# RaspberryPi3_Cape_V1_0.net
KiCad netlist of a schematic drawn in Altium Designer
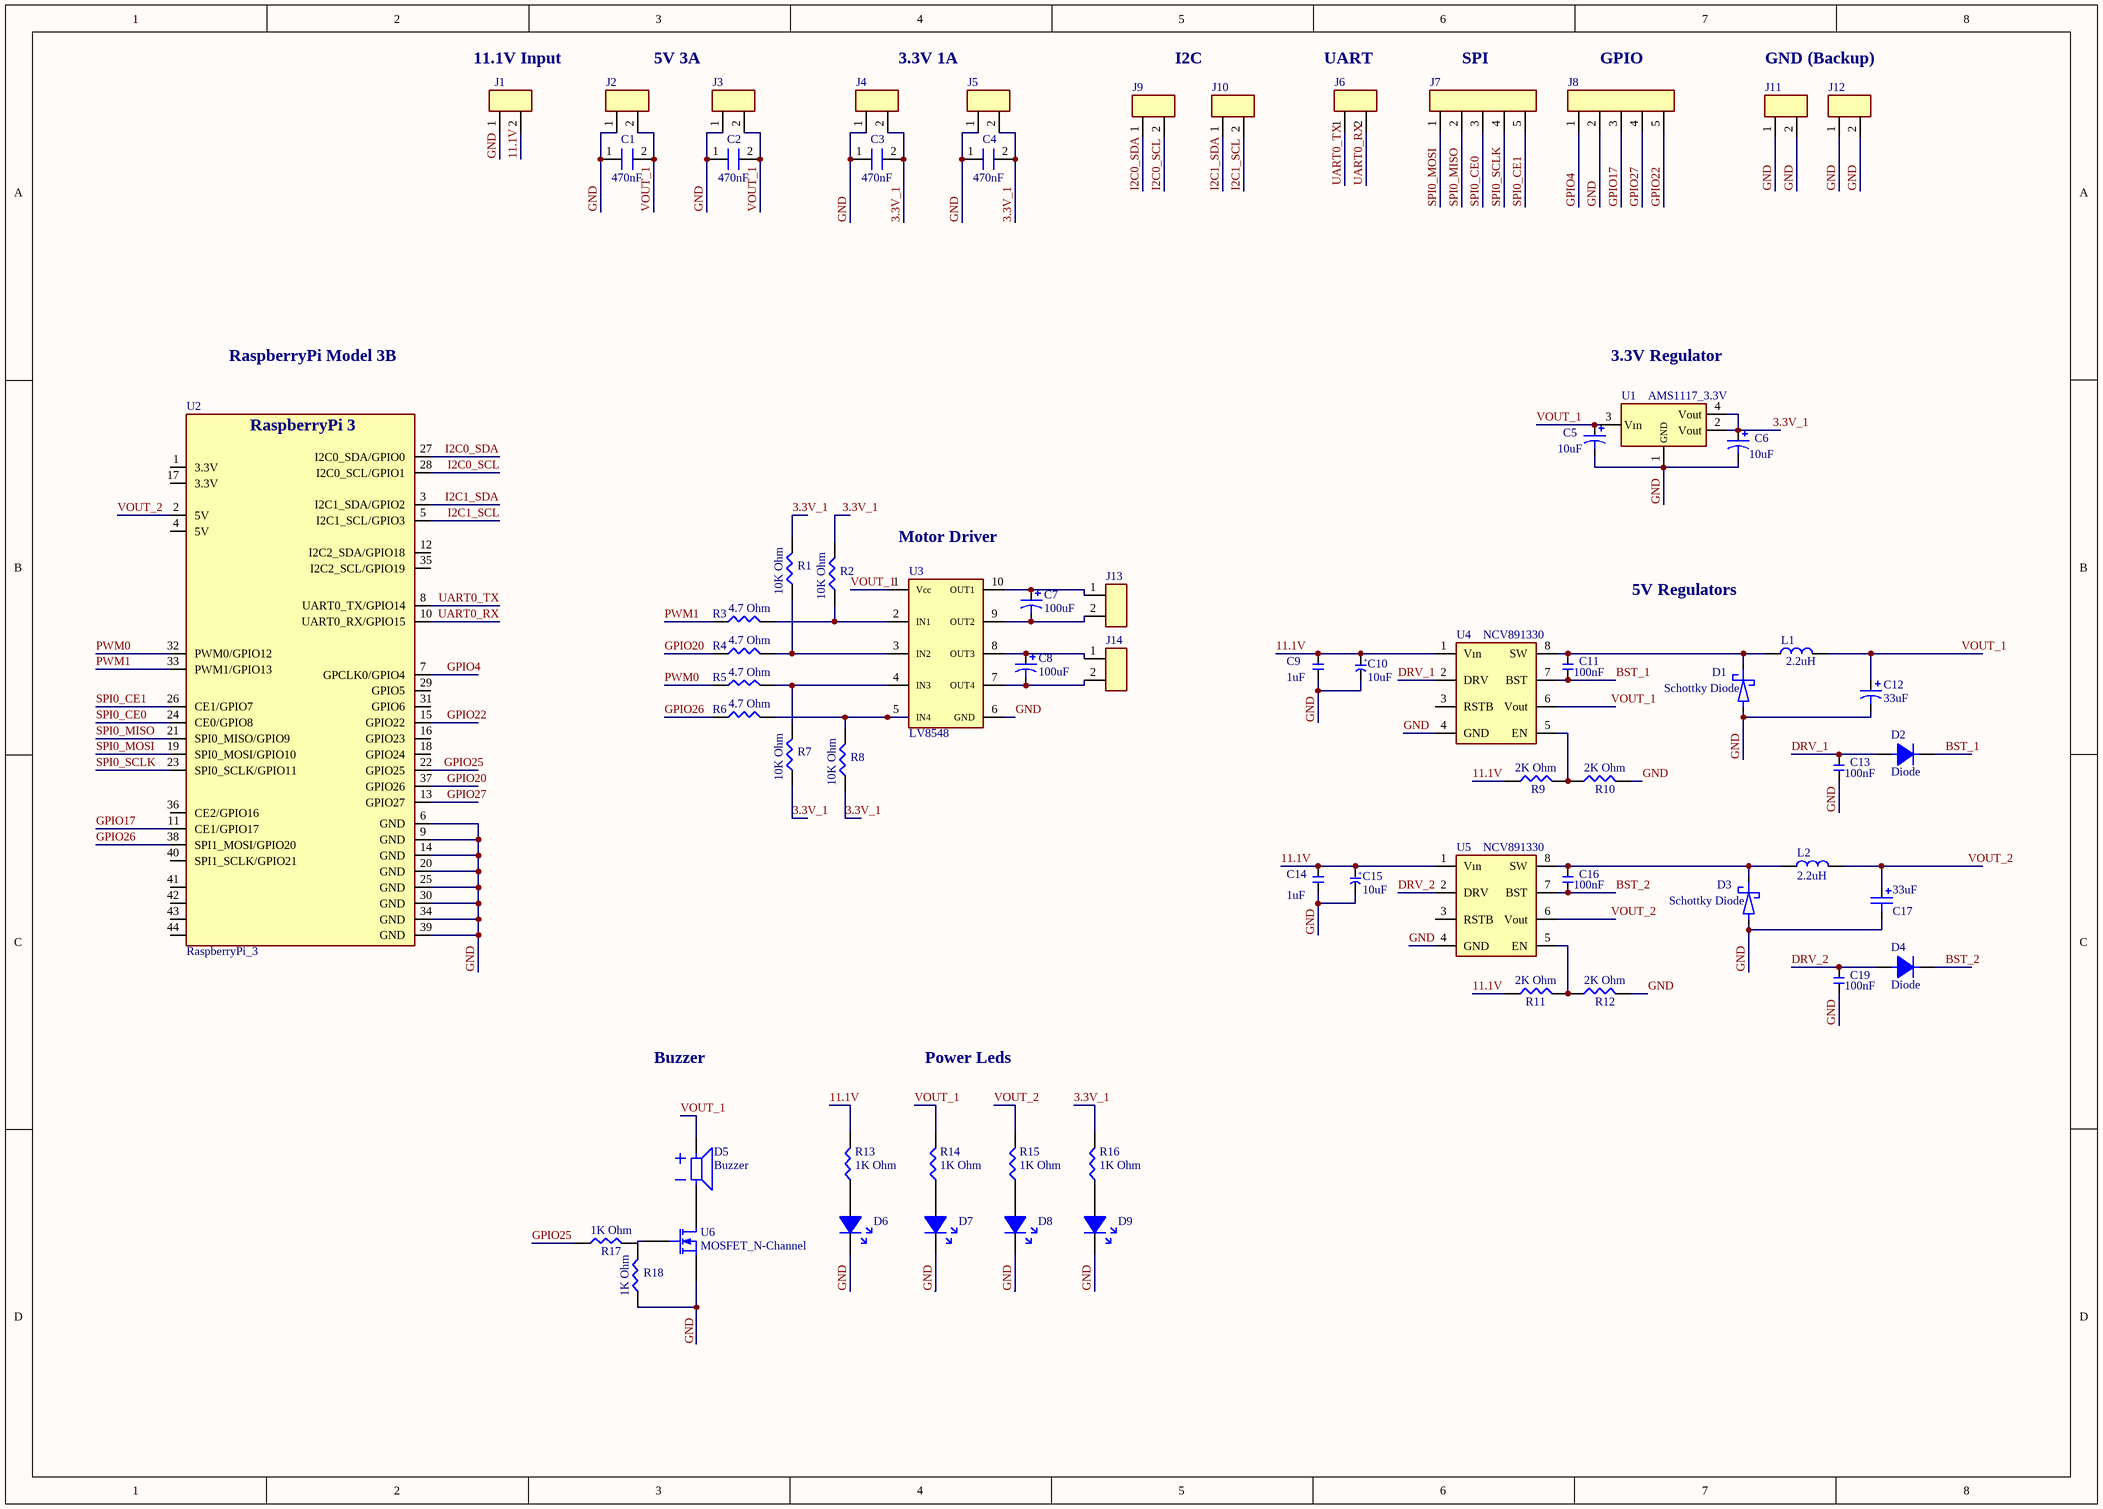
[diagram p0: RaspberryPi3_Cape_V1.0.SchDoc]

(export (version "E")
  (design (tool "Eeschema 10.0.6"))
  (components
    (comp (ref "C1")
      (value "470nF")
      (footprint "CAP_0805")
      (description "0805 Package SMD Capacitor")
      (libsource (lib "") (part "CAP_0805_1"))
    )
    (comp (ref "C2")
      (value "470nF")
      (footprint "CAP_0805")
      (description "0805 Package SMD Capacitor")
      (libsource (lib "") (part "CAP_0805_1"))
    )
    (comp (ref "C3")
      (value "470nF")
      (footprint "CAP_0805")
      (description "0805 Package SMD Capacitor")
      (libsource (lib "") (part "CAP_0805_1"))
    )
    (comp (ref "C4")
      (value "470nF")
      (footprint "CAP_0805")
      (description "0805 Package SMD Capacitor")
      (libsource (lib "") (part "CAP_0805_1"))
    )
    (comp (ref "C5")
      (value "10uF")
      (footprint "CAP_POL_P-1.5mm")
      (libsource (lib "Schlib1") (part "Cap_Polarized_1.5mm"))
    )
    (comp (ref "C6")
      (value "10uF")
      (footprint "CAP_POL_P-1.5mm")
      (libsource (lib "Schlib1") (part "Cap_Polarized_1.5mm"))
    )
    (comp (ref "C7")
      (value "100uF")
      (footprint "Cap_Pol_P-2mm")
      (description "Polarized Capacitor 2.5mm pitch")
      (libsource (lib "Schlib1") (part "Cap_Polarized"))
    )
    (comp (ref "C8")
      (value "100uF")
      (footprint "Cap_Pol_P-2mm")
      (description "Polarized Capacitor 2.5mm pitch")
      (libsource (lib "Schlib1") (part "Cap_Polarized"))
    )
    (comp (ref "C9")
      (value "1uF")
      (footprint "CAP_0805")
      (description "0805 Package SMD Capacitor")
      (libsource (lib "Schlib1.~(37).~(9)") (part "CAP_0805"))
    )
    (comp (ref "C10")
      (value "10uF")
      (footprint "CP_Radial_D5mm_L11mm_P2mm")
      (description "4x6 Radial Polarized Capacitor")
      (libsource (lib "Xbee_Co") (part "Cap_Pol_4x6"))
    )
    (comp (ref "C11")
      (value "100nF")
      (footprint "CAP_0805")
      (description "0805 Package SMD Capacitor")
      (libsource (lib "Schlib1.~(37).~(9)") (part "CAP_0805"))
    )
    (comp (ref "C12")
      (value "33uF")
      (footprint "Cap_Pol_P-2mm")
      (description "Polarized Capacitor 2.5mm pitch")
      (libsource (lib "Schlib1") (part "Cap_Polarized"))
    )
    (comp (ref "C13")
      (value "100nF")
      (footprint "CAP_0805")
      (description "0805 Package SMD Capacitor")
      (libsource (lib "Schlib1.~(37).~(9)") (part "CAP_0805"))
    )
    (comp (ref "C14")
      (value "1uF")
      (footprint "CAP_0805")
      (description "0805 Package SMD Capacitor")
      (libsource (lib "Schlib1.~(37).~(9)") (part "CAP_0805"))
    )
    (comp (ref "C15")
      (value "10uF")
      (footprint "CP_Radial_D5mm_L11mm_P2mm")
      (description "4x6 Radial Polarized Capacitor")
      (libsource (lib "Xbee_Co") (part "Cap_Pol_4x6"))
    )
    (comp (ref "C16")
      (value "100nF")
      (footprint "CAP_0805")
      (description "0805 Package SMD Capacitor")
      (libsource (lib "Schlib1.~(37).~(9)") (part "CAP_0805"))
    )
    (comp (ref "C17")
      (value "33uF")
      (footprint "SMD_Electrolytic_6.3x5.2")
      (libsource (lib "Schlib1.~(37).~(9)") (part "CAP_SMD_Electrolytic_6.3x5.4"))
    )
    (comp (ref "C19")
      (value "100nF")
      (footprint "CAP_0805")
      (description "0805 Package SMD Capacitor")
      (libsource (lib "Schlib1.~(37).~(9)") (part "CAP_0805"))
    )
    (comp (ref "D1")
      (value "Schottky Diode")
      (footprint "Schotty Diode")
      (description "1A,60V Schottky Diode")
      (libsource (lib "Schlib1.~(37).~(9)") (part "Schottky Diode"))
    )
    (comp (ref "D2")
      (value "Diode")
      (footprint "SOD323")
      (description "SOD323 Package Diode.")
      (libsource (lib "Schlib1.~(37).~(9)") (part "Diode"))
    )
    (comp (ref "D3")
      (value "Schottky Diode")
      (footprint "Schotty Diode")
      (description "1A,60V Schottky Diode")
      (libsource (lib "Schlib1.~(37).~(9)") (part "Schottky Diode"))
    )
    (comp (ref "D4")
      (value "Diode")
      (footprint "SOD323")
      (description "SOD323 Package Diode.")
      (libsource (lib "Schlib1.~(37).~(9)") (part "Diode"))
    )
    (comp (ref "D5") (value "Buzzer") (footprint "BUZZER") (libsource (lib "Schlib1") (part "Buzzer")))
    (comp (ref "D6")
      (value "LED")
      (footprint "Led_0805")
      (description "0805 Package SMD Led")
      (libsource (lib "Schlib1.~(37).~(9)") (part "LED_0805_2012"))
    )
    (comp (ref "D7")
      (value "LED")
      (footprint "Led_0805")
      (description "0805 Package SMD Led")
      (libsource (lib "Schlib1.~(37).~(9)") (part "LED_0805_2012"))
    )
    (comp (ref "D8")
      (value "LED")
      (footprint "Led_0805")
      (description "0805 Package SMD Led")
      (libsource (lib "Schlib1.~(37).~(9)") (part "LED_0805_2012"))
    )
    (comp (ref "D9")
      (value "LED")
      (footprint "Led_0805")
      (description "0805 Package SMD Led")
      (libsource (lib "Schlib1.~(37).~(9)") (part "LED_0805_2012"))
    )
    (comp (ref "J1")
      (value "JST_1x2_2.54mm")
      (footprint "JST_1x2_B2B_XH-A")
      (description "JST_1x2_2.54mm PCB Header")
      (libsource (lib "Schlib1.~(37).~(9)") (part "JST_1x2_2.54mm"))
    )
    (comp (ref "J2")
      (value "JST_1x2_2.54mm")
      (footprint "JST_1x2_B2B_XH-A")
      (description "JST_1x2_2.54mm PCB Header")
      (libsource (lib "Schlib1.~(37).~(9)") (part "JST_1x2_2.54mm"))
    )
    (comp (ref "J3")
      (value "JST_1x2_2.54mm")
      (footprint "JST_1x2_B2B_XH-A")
      (description "JST_1x2_2.54mm PCB Header")
      (libsource (lib "Schlib1.~(37).~(9)") (part "JST_1x2_2.54mm"))
    )
    (comp (ref "J4")
      (value "JST_1x2_2.54mm")
      (footprint "JST_1x2_B2B_XH-A")
      (description "JST_1x2_2.54mm PCB Header")
      (libsource (lib "Schlib1.~(37).~(9)") (part "JST_1x2_2.54mm"))
    )
    (comp (ref "J5")
      (value "JST_1x2_2.54mm")
      (footprint "JST_1x2_B2B_XH-A")
      (description "JST_1x2_2.54mm PCB Header")
      (libsource (lib "Schlib1.~(37).~(9)") (part "JST_1x2_2.54mm"))
    )
    (comp (ref "J6")
      (value "JST_1x2_2.54mm")
      (footprint "JST_1x2_B2B_XH-A")
      (description "JST_1x2_2.54mm PCB Header")
      (libsource (lib "Schlib1.~(37).~(9)") (part "JST_1x2_2.54mm"))
    )
    (comp (ref "J7")
      (value "JST_1x5_2.54mm")
      (footprint "JST_1x5_B2B_XH-A")
      (description "JST_1x5_2.54mm PCB Header")
      (libsource (lib "Schlib1.~(37).~(9)") (part "JST_1x5_2.54mm"))
    )
    (comp (ref "J8")
      (value "JST_1x5_2.54mm")
      (footprint "JST_1x5_B2B_XH-A")
      (description "JST_1x5_2.54mm PCB Header")
      (libsource (lib "Schlib1.~(37).~(9)") (part "JST_1x5_2.54mm"))
    )
    (comp (ref "J9")
      (value "JST_1x2_2.54mm")
      (footprint "JST_1x2_B2B_XH-A")
      (description "JST_1x2_2.54mm PCB Header")
      (libsource (lib "Schlib1.~(37).~(9)") (part "JST_1x2_2.54mm"))
    )
    (comp (ref "J10")
      (value "JST_1x2_2.54mm")
      (footprint "JST_1x2_B2B_XH-A")
      (description "JST_1x2_2.54mm PCB Header")
      (libsource (lib "Schlib1.~(37).~(9)") (part "JST_1x2_2.54mm"))
    )
    (comp (ref "J11")
      (value "JST_1x2_2.54mm")
      (footprint "JST_1x2_B2B_XH-A")
      (description "JST_1x2_2.54mm PCB Header")
      (libsource (lib "Schlib1.~(37).~(9)") (part "JST_1x2_2.54mm"))
    )
    (comp (ref "J12")
      (value "JST_1x2_2.54mm")
      (footprint "JST_1x2_B2B_XH-A")
      (description "JST_1x2_2.54mm PCB Header")
      (libsource (lib "Schlib1.~(37).~(9)") (part "JST_1x2_2.54mm"))
    )
    (comp (ref "J13")
      (value "JST_1x2_2.54mm")
      (footprint "JST_1x2_B2B_XH-A")
      (description "JST_1x2_2.54mm PCB Header")
      (libsource (lib "") (part "JST_1x2_2.54mm_1"))
    )
    (comp (ref "J14")
      (value "JST_1x2_2.54mm")
      (footprint "JST_1x2_B2B_XH-A")
      (description "JST_1x2_2.54mm PCB Header")
      (libsource (lib "") (part "JST_1x2_2.54mm_1"))
    )
    (comp (ref "L1")
      (value "2.2uH")
      (footprint "INDUCTOR")
      (libsource (lib "Schlib1.~(37).~(9)") (part "Inductor"))
    )
    (comp (ref "L2")
      (value "2.2uH")
      (footprint "INDUCTOR")
      (libsource (lib "Schlib1.~(37).~(9)") (part "Inductor"))
    )
    (comp (ref "R1")
      (value "10K Ohm")
      (footprint "RES_0805_2012")
      (description "0805 Package SMD Resistor")
      (libsource (lib "Schlib1.~(37).~(9)") (part "RES_0805_2012"))
    )
    (comp (ref "R2")
      (value "10K Ohm")
      (footprint "RES_0805_2012")
      (description "0805 Package SMD Resistor")
      (libsource (lib "Schlib1.~(37).~(9)") (part "RES_0805_2012"))
    )
    (comp (ref "R3")
      (value "4.7 Ohm")
      (footprint "RES_0805_2012")
      (description "0805 Package SMD Resistor")
      (libsource (lib "Schlib1.~(37).~(9)") (part "RES_0805_2012"))
    )
    (comp (ref "R4")
      (value "4.7 Ohm")
      (footprint "RES_0805_2012")
      (description "0805 Package SMD Resistor")
      (libsource (lib "Schlib1.~(37).~(9)") (part "RES_0805_2012"))
    )
    (comp (ref "R5")
      (value "4.7 Ohm")
      (footprint "RES_0805_2012")
      (description "0805 Package SMD Resistor")
      (libsource (lib "Schlib1.~(37).~(9)") (part "RES_0805_2012"))
    )
    (comp (ref "R6")
      (value "4.7 Ohm")
      (footprint "RES_0805_2012")
      (description "0805 Package SMD Resistor")
      (libsource (lib "Schlib1.~(37).~(9)") (part "RES_0805_2012"))
    )
    (comp (ref "R7")
      (value "10K Ohm")
      (footprint "RES_0805_2012")
      (description "0805 Package SMD Resistor")
      (libsource (lib "Schlib1.~(37).~(9)") (part "RES_0805_2012"))
    )
    (comp (ref "R8")
      (value "10K Ohm")
      (footprint "RES_0805_2012")
      (description "0805 Package SMD Resistor")
      (libsource (lib "Schlib1.~(37).~(9)") (part "RES_0805_2012"))
    )
    (comp (ref "R9")
      (value "2K Ohm")
      (footprint "RES_0805_2012")
      (description "0805 Package SMD Resistor")
      (libsource (lib "Schlib1.~(37).~(9)") (part "RES_0805_2012"))
    )
    (comp (ref "R10")
      (value "2K Ohm")
      (footprint "RES_0805_2012")
      (description "0805 Package SMD Resistor")
      (libsource (lib "Schlib1.~(37).~(9)") (part "RES_0805_2012"))
    )
    (comp (ref "R11")
      (value "2K Ohm")
      (footprint "RES_0805_2012")
      (description "0805 Package SMD Resistor")
      (libsource (lib "Schlib1.~(37).~(9)") (part "RES_0805_2012"))
    )
    (comp (ref "R12")
      (value "2K Ohm")
      (footprint "RES_0805_2012")
      (description "0805 Package SMD Resistor")
      (libsource (lib "Schlib1.~(37).~(9)") (part "RES_0805_2012"))
    )
    (comp (ref "R13")
      (value "1K Ohm")
      (footprint "RES_0805_2012")
      (description "0805 Package SMD Resistor")
      (libsource (lib "Schlib1.~(37).~(9)") (part "RES_0805_2012"))
    )
    (comp (ref "R14")
      (value "1K Ohm")
      (footprint "RES_0805_2012")
      (description "0805 Package SMD Resistor")
      (libsource (lib "Schlib1.~(37).~(9)") (part "RES_0805_2012"))
    )
    (comp (ref "R15")
      (value "1K Ohm")
      (footprint "RES_0805_2012")
      (description "0805 Package SMD Resistor")
      (libsource (lib "Schlib1.~(37).~(9)") (part "RES_0805_2012"))
    )
    (comp (ref "R16")
      (value "1K Ohm")
      (footprint "RES_0805_2012")
      (description "0805 Package SMD Resistor")
      (libsource (lib "Schlib1.~(37).~(9)") (part "RES_0805_2012"))
    )
    (comp (ref "R17")
      (value "1K Ohm")
      (footprint "RES_0805_2012")
      (description "0805 Package SMD Resistor")
      (libsource (lib "Schlib1.~(37).~(9)") (part "RES_0805_2012"))
    )
    (comp (ref "R18")
      (value "1K Ohm")
      (footprint "RES_0805_2012")
      (description "0805 Package SMD Resistor")
      (libsource (lib "Schlib1.~(37).~(9)") (part "RES_0805_2012"))
    )
    (comp (ref "U1")
      (value "AMS1117_3.3V")
      (footprint "SOT223_AMS")
      (description "Linear Regulator.         3.3V,1A Output.                        SOT-223 Package.")
      (libsource (lib "Schlib1.~(37).~(9)") (part "AMS1117_3.3V"))
    )
    (comp (ref "U2")
      (value "RaspberryPi_3")
      (footprint "Raspberry Pi 3 ModelB")
      (description "RaspberryPi 3+ Model B.")
      (libsource (lib "Schlib1.~(37).~(9)") (part "RaspberryPi_3"))
    )
    (comp (ref "U3")
      (value "LV8548")
      (footprint "SOIC10")
      (description "2-Channel Motor Driver.           SOIC-10 Package.")
      (libsource (lib "Schlib1.~(37).~(9)") (part "LV8548"))
    )
    (comp (ref "U4")
      (value "NCV891330")
      (footprint "SOIC8")
      (description "Switching Regulator.            5V, Max 3A Output.                         SOIC-8 Package.")
      (libsource (lib "Schlib1.~(37).~(9)") (part "NCV891330"))
    )
    (comp (ref "U5")
      (value "NCV891330")
      (footprint "SOIC8")
      (description "Switching Regulator.            5V, Max 3A Output.                         SOIC-8 Package.")
      (libsource (lib "Schlib1.~(37).~(9)") (part "NCV891330"))
    )
    (comp (ref "U6")
      (value "MOSFET_N-Channel")
      (footprint "SOT23")
      (description "500mA,60V N-Channel Mosfet.")
      (libsource (lib "Schlib1") (part "MOSFET_N-Channel"))
    )
  )
  (nets
    (net (code "1") (name "/3.3V_1") (class "Default")
      (node (ref "C3") (pin "2") (pinfunction "4_2") (pintype "passive"))
      (node (ref "C4") (pin "2") (pinfunction "4_2") (pintype "passive"))
      (node (ref "C6") (pin "1") (pinfunction "1_1") (pintype "passive"))
      (node (ref "J4") (pin "2") (pinfunction "1_2") (pintype "passive"))
      (node (ref "J5") (pin "2") (pinfunction "1_2") (pintype "passive"))
      (node (ref "R1") (pin "2") (pinfunction "7_2") (pintype "passive"))
      (node (ref "R16") (pin "2") (pinfunction "7_2") (pintype "passive"))
      (node (ref "R2") (pin "2") (pinfunction "7_2") (pintype "passive"))
      (node (ref "R7") (pin "1") (pinfunction "6_1") (pintype "passive"))
      (node (ref "R8") (pin "1") (pinfunction "6_1") (pintype "passive"))
      (node (ref "U1") (pin "2") (pinfunction "Vout_2") (pintype "passive"))
      (node (ref "U1") (pin "4") (pinfunction "Vout_4") (pintype "passive"))
    )
    (net (code "2") (name "/11.1V") (class "Default")
      (node (ref "C10") (pin "1") (pinfunction "11_1") (pintype "passive"))
      (node (ref "C14") (pin "2") (pinfunction "4_2") (pintype "passive"))
      (node (ref "C15") (pin "1") (pinfunction "11_1") (pintype "passive"))
      (node (ref "C9") (pin "2") (pinfunction "4_2") (pintype "passive"))
      (node (ref "J1") (pin "2") (pinfunction "1_2") (pintype "passive"))
      (node (ref "R11") (pin "1") (pinfunction "6_1") (pintype "passive"))
      (node (ref "R13") (pin "2") (pinfunction "7_2") (pintype "passive"))
      (node (ref "R9") (pin "1") (pinfunction "6_1") (pintype "passive"))
      (node (ref "U4") (pin "1") (pinfunction "Vın_1") (pintype "passive"))
      (node (ref "U5") (pin "1") (pinfunction "Vın_1") (pintype "passive"))
    )
    (net (code "3") (name "/BST_1") (class "Default")
      (node (ref "C11") (pin "1") (pinfunction "3_1") (pintype "passive"))
      (node (ref "D2") (pin "2") (pinfunction "2_2") (pintype "passive"))
      (node (ref "U4") (pin "7") (pinfunction "BST_7") (pintype "passive"))
    )
    (net (code "4") (name "/BST_2") (class "Default")
      (node (ref "C16") (pin "1") (pinfunction "3_1") (pintype "passive"))
      (node (ref "D4") (pin "2") (pinfunction "2_2") (pintype "passive"))
      (node (ref "U5") (pin "7") (pinfunction "BST_7") (pintype "passive"))
    )
    (net (code "5") (name "/DRV_1") (class "Default")
      (node (ref "C13") (pin "2") (pinfunction "4_2") (pintype "passive"))
      (node (ref "D2") (pin "1") (pinfunction "1_1") (pintype "passive"))
      (node (ref "U4") (pin "2") (pinfunction "DRV_2") (pintype "passive"))
    )
    (net (code "6") (name "/DRV_2") (class "Default")
      (node (ref "C19") (pin "2") (pinfunction "4_2") (pintype "passive"))
      (node (ref "D4") (pin "1") (pinfunction "1_1") (pintype "passive"))
      (node (ref "U5") (pin "2") (pinfunction "DRV_2") (pintype "passive"))
    )
    (net (code "7") (name "/GND") (class "Default")
      (node (ref "C1") (pin "1") (pinfunction "3_1") (pintype "passive"))
      (node (ref "C10") (pin "2") (pinfunction "12_2") (pintype "passive"))
      (node (ref "C12") (pin "2") (pinfunction "2_2") (pintype "passive"))
      (node (ref "C13") (pin "1") (pinfunction "3_1") (pintype "passive"))
      (node (ref "C14") (pin "1") (pinfunction "3_1") (pintype "passive"))
      (node (ref "C15") (pin "2") (pinfunction "12_2") (pintype "passive"))
      (node (ref "C17") (pin "2") (pinfunction "2_2") (pintype "passive"))
      (node (ref "C19") (pin "1") (pinfunction "3_1") (pintype "passive"))
      (node (ref "C2") (pin "1") (pinfunction "3_1") (pintype "passive"))
      (node (ref "C3") (pin "1") (pinfunction "3_1") (pintype "passive"))
      (node (ref "C4") (pin "1") (pinfunction "3_1") (pintype "passive"))
      (node (ref "C5") (pin "2") (pinfunction "2_2") (pintype "passive"))
      (node (ref "C6") (pin "2") (pinfunction "2_2") (pintype "passive"))
      (node (ref "C9") (pin "1") (pinfunction "3_1") (pintype "passive"))
      (node (ref "D1") (pin "1") (pinfunction "1_1") (pintype "passive"))
      (node (ref "D3") (pin "1") (pinfunction "1_1") (pintype "passive"))
      (node (ref "D6") (pin "2") (pinfunction "2_2") (pintype "passive"))
      (node (ref "D7") (pin "2") (pinfunction "2_2") (pintype "passive"))
      (node (ref "D8") (pin "2") (pinfunction "2_2") (pintype "passive"))
      (node (ref "D9") (pin "2") (pinfunction "2_2") (pintype "passive"))
      (node (ref "J1") (pin "1") (pinfunction "0_1") (pintype "passive"))
      (node (ref "J11") (pin "1") (pinfunction "0_1") (pintype "passive"))
      (node (ref "J11") (pin "2") (pinfunction "1_2") (pintype "passive"))
      (node (ref "J12") (pin "1") (pinfunction "0_1") (pintype "passive"))
      (node (ref "J12") (pin "2") (pinfunction "1_2") (pintype "passive"))
      (node (ref "J2") (pin "1") (pinfunction "0_1") (pintype "passive"))
      (node (ref "J3") (pin "1") (pinfunction "0_1") (pintype "passive"))
      (node (ref "J4") (pin "1") (pinfunction "0_1") (pintype "passive"))
      (node (ref "J5") (pin "1") (pinfunction "0_1") (pintype "passive"))
      (node (ref "J8") (pin "2") (pinfunction "1_2") (pintype "passive"))
      (node (ref "R10") (pin "2") (pinfunction "7_2") (pintype "passive"))
      (node (ref "R12") (pin "2") (pinfunction "7_2") (pintype "passive"))
      (node (ref "U1") (pin "1") (pinfunction "GND_1") (pintype "passive"))
      (node (ref "U2") (pin "14") (pinfunction "GND_14") (pintype "passive"))
      (node (ref "U2") (pin "20") (pinfunction "GND_20") (pintype "passive"))
      (node (ref "U2") (pin "25") (pinfunction "GND_25") (pintype "passive"))
      (node (ref "U2") (pin "30") (pinfunction "GND_30") (pintype "passive"))
      (node (ref "U2") (pin "34") (pinfunction "GND_34") (pintype "passive"))
      (node (ref "U2") (pin "39") (pinfunction "GND_39") (pintype "passive"))
      (node (ref "U2") (pin "6") (pinfunction "GND_6") (pintype "passive"))
      (node (ref "U2") (pin "9") (pinfunction "GND_9") (pintype "passive"))
      (node (ref "U3") (pin "6") (pinfunction "GND_6") (pintype "passive"))
      (node (ref "U4") (pin "4") (pinfunction "GND_4") (pintype "passive"))
      (node (ref "U5") (pin "4") (pinfunction "GND_4") (pintype "passive"))
    )
    (net (code "8") (name "/GPIO4") (class "Default")
      (node (ref "J8") (pin "1") (pinfunction "0_1") (pintype "passive"))
      (node (ref "U2") (pin "7") (pinfunction "GPCLK0/GPIO4_7") (pintype "passive"))
    )
    (net (code "9") (name "/GPIO17") (class "Default")
      (node (ref "J8") (pin "3") (pinfunction "3_3") (pintype "passive"))
      (node (ref "U2") (pin "11") (pinfunction "CE1/GPIO17_11") (pintype "passive"))
    )
    (net (code "10") (name "/GPIO20") (class "Default")
      (node (ref "R4") (pin "1") (pinfunction "6_1") (pintype "passive"))
      (node (ref "U2") (pin "37") (pinfunction "GPIO26_37") (pintype "passive"))
    )
    (net (code "11") (name "/GPIO22") (class "Default")
      (node (ref "J8") (pin "5") (pinfunction "5_5") (pintype "passive"))
      (node (ref "U2") (pin "15") (pinfunction "GPIO22_15") (pintype "passive"))
    )
    (net (code "12") (name "/GPIO25") (class "Default")
      (node (ref "R17") (pin "1") (pinfunction "6_1") (pintype "passive"))
      (node (ref "U2") (pin "22") (pinfunction "GPIO25_22") (pintype "passive"))
    )
    (net (code "13") (name "/GPIO26") (class "Default")
      (node (ref "R6") (pin "1") (pinfunction "6_1") (pintype "passive"))
      (node (ref "U2") (pin "38") (pinfunction "SPI1_MOSI/GPIO20_38") (pintype "passive"))
    )
    (net (code "14") (name "/GPIO27") (class "Default")
      (node (ref "J8") (pin "4") (pinfunction "4_4") (pintype "passive"))
      (node (ref "U2") (pin "13") (pinfunction "GPIO27_13") (pintype "passive"))
    )
    (net (code "15") (name "/I2C0_SCL") (class "Default")
      (node (ref "J9") (pin "2") (pinfunction "1_2") (pintype "passive"))
      (node (ref "U2") (pin "28") (pinfunction "I2C0_SCL/GPIO1_28") (pintype "passive"))
    )
    (net (code "16") (name "/I2C0_SDA") (class "Default")
      (node (ref "J9") (pin "1") (pinfunction "0_1") (pintype "passive"))
      (node (ref "U2") (pin "27") (pinfunction "I2C0_SDA/GPIO0_27") (pintype "passive"))
    )
    (net (code "17") (name "/I2C1_SCL") (class "Default")
      (node (ref "J10") (pin "2") (pinfunction "1_2") (pintype "passive"))
      (node (ref "U2") (pin "5") (pinfunction "I2C1_SCL/GPIO3_5") (pintype "passive"))
    )
    (net (code "18") (name "/I2C1_SDA") (class "Default")
      (node (ref "J10") (pin "1") (pinfunction "0_1") (pintype "passive"))
      (node (ref "U2") (pin "3") (pinfunction "I2C1_SDA/GPIO2_3") (pintype "passive"))
    )
    (net (code "19") (name "/PWM0") (class "Default")
      (node (ref "R5") (pin "1") (pinfunction "6_1") (pintype "passive"))
      (node (ref "U2") (pin "32") (pinfunction "PWM0/GPIO12_32") (pintype "passive"))
    )
    (net (code "20") (name "/PWM1") (class "Default")
      (node (ref "R3") (pin "1") (pinfunction "6_1") (pintype "passive"))
      (node (ref "U2") (pin "33") (pinfunction "PWM1/GPIO13_33") (pintype "passive"))
    )
    (net (code "21") (name "/SPI0_CE0") (class "Default")
      (node (ref "J7") (pin "3") (pinfunction "3_3") (pintype "passive"))
      (node (ref "U2") (pin "24") (pinfunction "CE0/GPIO8_24") (pintype "passive"))
    )
    (net (code "22") (name "/SPI0_CE1") (class "Default")
      (node (ref "J7") (pin "5") (pinfunction "5_5") (pintype "passive"))
      (node (ref "U2") (pin "26") (pinfunction "CE1/GPIO7_26") (pintype "passive"))
    )
    (net (code "23") (name "/SPI0_MISO") (class "Default")
      (node (ref "J7") (pin "2") (pinfunction "1_2") (pintype "passive"))
      (node (ref "U2") (pin "21") (pinfunction "SPI0_MISO/GPIO9_21") (pintype "passive"))
    )
    (net (code "24") (name "/SPI0_MOSI") (class "Default")
      (node (ref "J7") (pin "1") (pinfunction "0_1") (pintype "passive"))
      (node (ref "U2") (pin "19") (pinfunction "SPI0_MOSI/GPIO10_19") (pintype "passive"))
    )
    (net (code "25") (name "/SPI0_SCLK") (class "Default")
      (node (ref "J7") (pin "4") (pinfunction "4_4") (pintype "passive"))
      (node (ref "U2") (pin "23") (pinfunction "SPI0_SCLK/GPIO11_23") (pintype "passive"))
    )
    (net (code "26") (name "/UART0_RX") (class "Default")
      (node (ref "J6") (pin "2") (pinfunction "1_2") (pintype "passive"))
      (node (ref "U2") (pin "10") (pinfunction "UART0_RX/GPIO15_10") (pintype "passive"))
    )
    (net (code "27") (name "/UART0_TX") (class "Default")
      (node (ref "J6") (pin "1") (pinfunction "0_1") (pintype "passive"))
      (node (ref "U2") (pin "8") (pinfunction "UART0_TX/GPIO14_8") (pintype "passive"))
    )
    (net (code "28") (name "/VOUT_1") (class "Default")
      (node (ref "C1") (pin "2") (pinfunction "4_2") (pintype "passive"))
      (node (ref "C12") (pin "1") (pinfunction "1_1") (pintype "passive"))
      (node (ref "C2") (pin "2") (pinfunction "4_2") (pintype "passive"))
      (node (ref "C5") (pin "1") (pinfunction "1_1") (pintype "passive"))
      (node (ref "D5") (pin "1") (pinfunction "1_1") (pintype "passive"))
      (node (ref "J2") (pin "2") (pinfunction "1_2") (pintype "passive"))
      (node (ref "J3") (pin "2") (pinfunction "1_2") (pintype "passive"))
      (node (ref "L1") (pin "2") (pinfunction "2_2") (pintype "passive"))
      (node (ref "R14") (pin "2") (pinfunction "7_2") (pintype "passive"))
      (node (ref "U1") (pin "3") (pinfunction "Vın_3") (pintype "passive"))
      (node (ref "U3") (pin "1") (pinfunction "Vcc_1") (pintype "passive"))
      (node (ref "U4") (pin "6") (pinfunction "Vout_6") (pintype "passive"))
    )
    (net (code "29") (name "/VOUT_2") (class "Default")
      (node (ref "C17") (pin "1") (pinfunction "1_1") (pintype "passive"))
      (node (ref "L2") (pin "2") (pinfunction "2_2") (pintype "passive"))
      (node (ref "R15") (pin "2") (pinfunction "7_2") (pintype "passive"))
      (node (ref "U2") (pin "2") (pinfunction "5V_2") (pintype "passive"))
      (node (ref "U5") (pin "6") (pinfunction "Vout_6") (pintype "passive"))
    )
    (net (code "30") (name "Net-(C11-4)") (class "Default")
      (node (ref "C11") (pin "2") (pinfunction "4_2") (pintype "passive"))
      (node (ref "D1") (pin "2") (pinfunction "2_2") (pintype "passive"))
      (node (ref "L1") (pin "1") (pinfunction "1_1") (pintype "passive"))
      (node (ref "U4") (pin "8") (pinfunction "SW_8") (pintype "passive"))
    )
    (net (code "31") (name "Net-(C16-4)") (class "Default")
      (node (ref "C16") (pin "2") (pinfunction "4_2") (pintype "passive"))
      (node (ref "D3") (pin "2") (pinfunction "2_2") (pintype "passive"))
      (node (ref "L2") (pin "1") (pinfunction "1_1") (pintype "passive"))
      (node (ref "U5") (pin "8") (pinfunction "SW_8") (pintype "passive"))
    )
    (net (code "32") (name "Net-(D6-8)") (class "Default")
      (node (ref "D6") (pin "1") (pinfunction "8_1") (pintype "passive"))
      (node (ref "R13") (pin "1") (pinfunction "6_1") (pintype "passive"))
    )
    (net (code "33") (name "Net-(D7-8)") (class "Default")
      (node (ref "D7") (pin "1") (pinfunction "8_1") (pintype "passive"))
      (node (ref "R14") (pin "1") (pinfunction "6_1") (pintype "passive"))
    )
    (net (code "34") (name "Net-(D8-8)") (class "Default")
      (node (ref "D8") (pin "1") (pinfunction "8_1") (pintype "passive"))
      (node (ref "R15") (pin "1") (pinfunction "6_1") (pintype "passive"))
    )
    (net (code "35") (name "Net-(D9-8)") (class "Default")
      (node (ref "D9") (pin "1") (pinfunction "8_1") (pintype "passive"))
      (node (ref "R16") (pin "1") (pinfunction "6_1") (pintype "passive"))
    )
    (net (code "36") (name "Net-(J13-0)") (class "Default")
      (node (ref "C7") (pin "1") (pinfunction "1_1") (pintype "passive"))
      (node (ref "J13") (pin "1") (pinfunction "0_1") (pintype "passive"))
      (node (ref "U3") (pin "10") (pinfunction "OUT1_10") (pintype "passive"))
    )
    (net (code "37") (name "Net-(J13-1)") (class "Default")
      (node (ref "C7") (pin "2") (pinfunction "2_2") (pintype "passive"))
      (node (ref "J13") (pin "2") (pinfunction "1_2") (pintype "passive"))
      (node (ref "U3") (pin "9") (pinfunction "OUT2_9") (pintype "passive"))
    )
    (net (code "38") (name "Net-(J14-0)") (class "Default")
      (node (ref "C8") (pin "1") (pinfunction "1_1") (pintype "passive"))
      (node (ref "J14") (pin "1") (pinfunction "0_1") (pintype "passive"))
      (node (ref "U3") (pin "8") (pinfunction "OUT3_8") (pintype "passive"))
    )
    (net (code "39") (name "Net-(J14-1)") (class "Default")
      (node (ref "C8") (pin "2") (pinfunction "2_2") (pintype "passive"))
      (node (ref "J14") (pin "2") (pinfunction "1_2") (pintype "passive"))
      (node (ref "U3") (pin "7") (pinfunction "OUT4_7") (pintype "passive"))
    )
    (net (code "40") (name "Net-(R1-6)") (class "Default")
      (node (ref "R1") (pin "1") (pinfunction "6_1") (pintype "passive"))
      (node (ref "R4") (pin "2") (pinfunction "7_2") (pintype "passive"))
      (node (ref "U3") (pin "3") (pinfunction "IN2_3") (pintype "passive"))
    )
    (net (code "41") (name "Net-(R2-6)") (class "Default")
      (node (ref "R2") (pin "1") (pinfunction "6_1") (pintype "passive"))
      (node (ref "R3") (pin "2") (pinfunction "7_2") (pintype "passive"))
      (node (ref "U3") (pin "2") (pinfunction "IN1_2") (pintype "passive"))
    )
    (net (code "42") (name "Net-(R5-7)") (class "Default")
      (node (ref "R5") (pin "2") (pinfunction "7_2") (pintype "passive"))
      (node (ref "R7") (pin "2") (pinfunction "7_2") (pintype "passive"))
      (node (ref "U3") (pin "4") (pinfunction "IN3_4") (pintype "passive"))
    )
    (net (code "43") (name "Net-(R6-7)") (class "Default")
      (node (ref "R6") (pin "2") (pinfunction "7_2") (pintype "passive"))
      (node (ref "R8") (pin "2") (pinfunction "7_2") (pintype "passive"))
      (node (ref "U3") (pin "5") (pinfunction "IN4_5") (pintype "passive"))
    )
    (net (code "44") (name "Net-(R10-6)") (class "Default")
      (node (ref "R10") (pin "1") (pinfunction "6_1") (pintype "passive"))
      (node (ref "R9") (pin "2") (pinfunction "7_2") (pintype "passive"))
      (node (ref "U4") (pin "5") (pinfunction "EN_5") (pintype "passive"))
    )
    (net (code "45") (name "Net-(R11-7)") (class "Default")
      (node (ref "R11") (pin "2") (pinfunction "7_2") (pintype "passive"))
      (node (ref "R12") (pin "1") (pinfunction "6_1") (pintype "passive"))
      (node (ref "U5") (pin "5") (pinfunction "EN_5") (pintype "passive"))
    )
    (net (code "46") (name "Net-(R17-7)") (class "Default")
      (node (ref "R17") (pin "2") (pinfunction "7_2") (pintype "passive"))
      (node (ref "R18") (pin "2") (pinfunction "7_2") (pintype "passive"))
      (node (ref "U6") (pin "1") (pinfunction "G_1") (pintype "passive"))
    )
    (net (code "47") (name "Net-(R18-6)") (class "Default")
      (node (ref "R18") (pin "1") (pinfunction "6_1") (pintype "passive"))
      (node (ref "U6") (pin "2") (pinfunction "S_2") (pintype "passive"))
    )
    (net (code "48") (name "Net-(U6-D)") (class "Default")
      (node (ref "D5") (pin "2") (pinfunction "2_2") (pintype "passive"))
      (node (ref "U6") (pin "3") (pinfunction "D_3") (pintype "passive"))
    )
    (net (code "49") (name "unconnected-(U2-3.3V-Pad1)") (class "Default")
      (node (ref "U2") (pin "1") (pinfunction "3.3V_1") (pintype "passive"))
    )
    (net (code "50") (name "unconnected-(U2-3.3V-Pad17)") (class "Default")
      (node (ref "U2") (pin "17") (pinfunction "3.3V_17") (pintype "passive"))
    )
    (net (code "51") (name "unconnected-(U2-5V-Pad4)") (class "Default")
      (node (ref "U2") (pin "4") (pinfunction "5V_4") (pintype "passive"))
    )
    (net (code "52") (name "unconnected-(U2-CE2{slash}GPIO16-Pad36)") (class "Default")
      (node (ref "U2") (pin "36") (pinfunction "CE2/GPIO16_36") (pintype "passive"))
    )
    (net (code "53") (name "unconnected-(U2-GPIO5-Pad29)") (class "Default")
      (node (ref "U2") (pin "29") (pinfunction "GPIO5_29") (pintype "passive"))
    )
    (net (code "54") (name "unconnected-(U2-GPIO6-Pad31)") (class "Default")
      (node (ref "U2") (pin "31") (pinfunction "GPIO6_31") (pintype "passive"))
    )
    (net (code "55") (name "unconnected-(U2-GPIO23-Pad16)") (class "Default")
      (node (ref "U2") (pin "16") (pinfunction "GPIO23_16") (pintype "passive"))
    )
    (net (code "56") (name "unconnected-(U2-GPIO24-Pad18)") (class "Default")
      (node (ref "U2") (pin "18") (pinfunction "GPIO24_18") (pintype "passive"))
    )
    (net (code "57") (name "unconnected-(U2-I2C2_SCL{slash}GPIO19-Pad35)") (class "Default")
      (node (ref "U2") (pin "35") (pinfunction "I2C2_SCL/GPIO19_35") (pintype "passive"))
    )
    (net (code "58") (name "unconnected-(U2-I2C2_SDA{slash}GPIO18-Pad12)") (class "Default")
      (node (ref "U2") (pin "12") (pinfunction "I2C2_SDA/GPIO18_12") (pintype "passive"))
    )
    (net (code "59") (name "unconnected-(U2-Pad41)") (class "Default")
      (node (ref "U2") (pin "41") (pinfunction "41_41") (pintype "passive"))
    )
    (net (code "60") (name "unconnected-(U2-Pad42)") (class "Default")
      (node (ref "U2") (pin "42") (pinfunction "42_42") (pintype "passive"))
    )
    (net (code "61") (name "unconnected-(U2-Pad43)") (class "Default")
      (node (ref "U2") (pin "43") (pinfunction "43_43") (pintype "passive"))
    )
    (net (code "62") (name "unconnected-(U2-Pad44)") (class "Default")
      (node (ref "U2") (pin "44") (pinfunction "44_44") (pintype "passive"))
    )
    (net (code "63") (name "unconnected-(U2-SPI1_SCLK{slash}GPIO21-Pad40)") (class "Default")
      (node (ref "U2") (pin "40") (pinfunction "SPI1_SCLK/GPIO21_40") (pintype "passive"))
    )
    (net (code "64") (name "unconnected-(U4-RSTB-Pad3)") (class "Default")
      (node (ref "U4") (pin "3") (pinfunction "RSTB_3") (pintype "passive"))
    )
    (net (code "65") (name "unconnected-(U5-RSTB-Pad3)") (class "Default")
      (node (ref "U5") (pin "3") (pinfunction "RSTB_3") (pintype "passive"))
    )
  )
)
